# DAC.net
KiCad netlist of a schematic drawn in Altium Designer
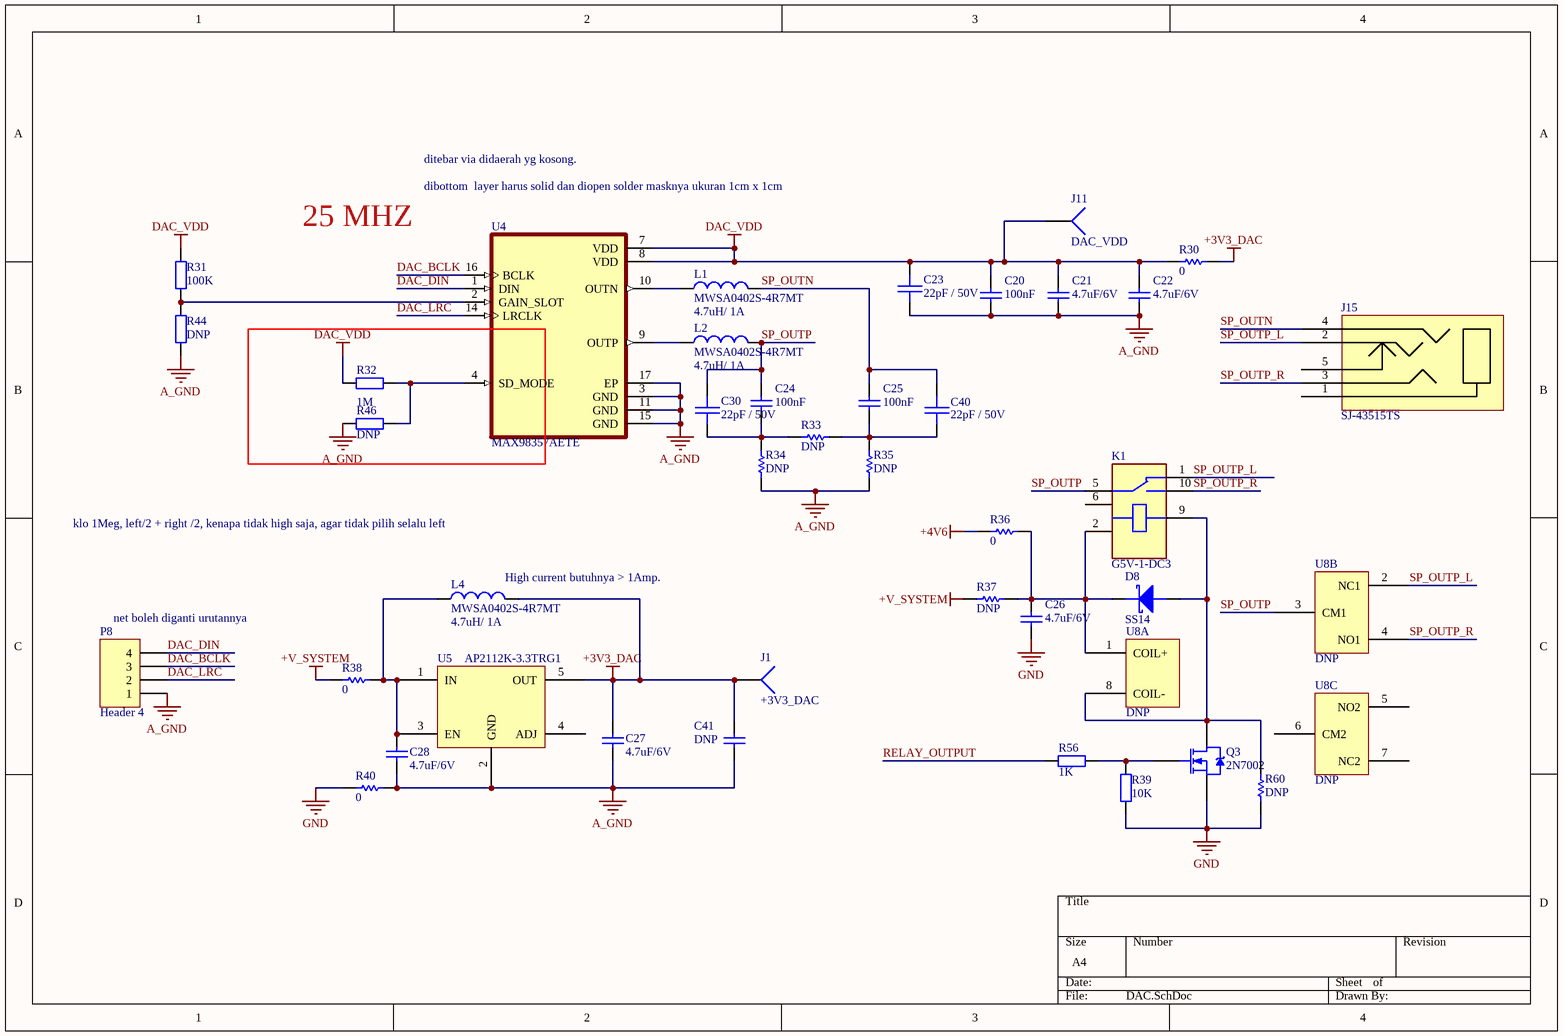
[diagram p0: DAC.SchDoc]

(export (version "E")
  (design (tool "Eeschema 10.0.6"))
  (components
    (comp (ref "C20")
      (value "100nF")
      (footprint "CR2012-0805")
      (description "Capacitor")
      (fields (field (name "PUBLISHER") "Altium Limited"))
      (libsource (lib "Miscellaneous Devices") (part "Cap"))
    )
    (comp (ref "C21")
      (value "4.7uF/6V")
      (footprint "CR2012-0805")
      (description "Capacitor")
      (fields (field (name "PUBLISHER") "Altium Limited"))
      (libsource (lib "Miscellaneous Devices") (part "Cap"))
    )
    (comp (ref "C22")
      (value "4.7uF/6V")
      (footprint "CR2012-0805")
      (description "Capacitor")
      (fields (field (name "PUBLISHER") "Altium Limited"))
      (libsource (lib "Miscellaneous Devices") (part "Cap"))
    )
    (comp (ref "C23")
      (value "22pF / 50V")
      (footprint "CR2012-0805")
      (description "Surface mount capacitor 0402")
      (libsource (lib "Vowstar_Basic_Device") (part "SMT_C_0402"))
    )
    (comp (ref "C24")
      (value "100nF")
      (footprint "CR2012-0805")
      (description "Capacitor")
      (fields (field (name "PUBLISHER") "Altium Limited"))
      (libsource (lib "Miscellaneous Devices") (part "Cap"))
    )
    (comp (ref "C25")
      (value "100nF")
      (footprint "CR2012-0805")
      (description "Capacitor")
      (fields (field (name "PUBLISHER") "Altium Limited"))
      (libsource (lib "Miscellaneous Devices") (part "Cap"))
    )
    (comp (ref "C26")
      (value "4.7uF/6V")
      (footprint "CR2012-0805")
      (description "Capacitor")
      (fields (field (name "PUBLISHER") "Altium Limited"))
      (libsource (lib "Miscellaneous Devices") (part "Cap"))
    )
    (comp (ref "C27")
      (value "4.7uF/6V")
      (footprint "CR2012-0805")
      (description "Capacitor (Semiconductor SIM Model)")
      (fields (field (name "PUBLISHER") "Altium Limited"))
      (libsource (lib "passive") (part "Cap Semi"))
    )
    (comp (ref "C28")
      (value "4.7uF/6V")
      (footprint "CR2012-0805")
      (description "Capacitor (Semiconductor SIM Model)")
      (fields (field (name "PUBLISHER") "Altium Limited"))
      (libsource (lib "passive") (part "Cap Semi"))
    )
    (comp (ref "C30")
      (value "22pF / 50V")
      (footprint "CR2012-0805")
      (description "Surface mount capacitor 0402")
      (libsource (lib "Vowstar_Basic_Device") (part "SMT_C_0402"))
    )
    (comp (ref "C40")
      (value "22pF / 50V")
      (footprint "CR2012-0805")
      (description "Surface mount capacitor 0402")
      (libsource (lib "Vowstar_Basic_Device") (part "SMT_C_0402"))
    )
    (comp (ref "C41")
      (value "DNP")
      (footprint "CR2012-0805")
      (description "Capacitor")
      (fields (field (name "PUBLISHER") "Altium Limited"))
      (libsource (lib "Miscellaneous Devices") (part "Cap"))
    )
    (comp (ref "D8")
      (value "SS14")
      (footprint "DO-214AC (SMA)")
      (description "Schottky Barrier Diodes")
      (fields (field (name "MANUFACTURER PART NUMBER") "SS18"))
      (libsource (lib "H2SCHALTIUM") (part "DIODE SCHOTTKY"))
    )
    (comp (ref "J1")
      (value "+3V3_DAC")
      (footprint "PIN1")
      (description "Socket")
      (fields (field (name "PUBLISHER") "Altium Limited"))
      (libsource (lib "Miscellaneous Connectors") (part "Socket"))
    )
    (comp (ref "J11")
      (value "DAC_VDD")
      (footprint "PIN1")
      (description "Socket")
      (fields (field (name "PUBLISHER") "Altium Limited"))
      (libsource (lib "Miscellaneous Connectors") (part "Socket"))
    )
    (comp (ref "J15")
      (value "SJ-43515TS")
      (footprint "SJ-435116")
      (description "SJ-43515TS 3.5 MM AUDIO JACK")
      (libsource (lib "passive") (part "SJ-43515TS"))
    )
    (comp (ref "K1")
      (value "G5V-1-DC3")
      (footprint "RELAY_G5V-1-DC5")
      (description "General Purpose Relay SPDT _1 Form C_ Through Hole")
      (fields (field (name "MF") "Omron Electronics") (field (name "MP") "G5V-1-DC5"))
      (libsource (lib "G5V-1-DC5") (part "G5V-1-DC5"))
    )
    (comp (ref "L1")
      (value "MWSA0402S-4R7MT")
      (footprint "IND4X4MM")
      (description "Inductor")
      (fields (field (name "ALTIUM_VALUE") "4.7uH/ 1A") (field (name "PUBLISHER") "Altium Limited"))
      (libsource (lib "passive") (part "Inductor"))
    )
    (comp (ref "L2")
      (value "MWSA0402S-4R7MT")
      (footprint "IND4X4MM")
      (description "Inductor")
      (fields (field (name "ALTIUM_VALUE") "4.7uH/ 1A") (field (name "PUBLISHER") "Altium Limited"))
      (libsource (lib "passive") (part "Inductor"))
    )
    (comp (ref "L4")
      (value "MWSA0402S-4R7MT")
      (footprint "IND4X4MM")
      (description "Inductor")
      (fields (field (name "ALTIUM_VALUE") "4.7uH/ 1A") (field (name "PUBLISHER") "Altium Limited"))
      (libsource (lib "passive") (part "Inductor"))
    )
    (comp (ref "P8")
      (value "Header 4")
      (footprint "HDR1X4")
      (description "Header, 4-Pin")
      (fields (field (name "PUBLISHER") "Altium Limited"))
      (libsource (lib "Miscellaneous Connectors") (part "Header 4"))
    )
    (comp (ref "Q3")
      (value "2N7002")
      (footprint "SOT-23/F2")
      (description "N CHANNEL MOSFET GENERIC SCH LIB")
      (fields (field (name "PART NUMBER") "2N7002ET1G") (field (name "MANUFACTURER") "ON Semiconductor"))
      (libsource (lib "passive") (part "NMOS_GENERIC_SOT23"))
    )
    (comp (ref "R30")
      (value "0")
      (footprint "JP1_SMD")
      (description "Semiconductor Resistor")
      (fields (field (name "PUBLISHER") "Altium Limited"))
      (libsource (lib "passive") (part "Res Semi"))
    )
    (comp (ref "R31")
      (value "100K")
      (footprint "JP2_SMD")
      (description "Resistor")
      (fields (field (name "PUBLISHER") "Altium Limited"))
      (libsource (lib "Miscellaneous Devices") (part "Res2"))
    )
    (comp (ref "R32")
      (value "1M")
      (footprint "JP2_SMD")
      (description "Resistor")
      (fields (field (name "PUBLISHER") "Altium Limited"))
      (libsource (lib "") (part "Res2_2"))
    )
    (comp (ref "R33")
      (value "DNP")
      (footprint "JP2_SMD")
      (description "Semiconductor Resistor")
      (fields (field (name "PUBLISHER") "Altium Limited"))
      (libsource (lib "passive") (part "Res Semi"))
    )
    (comp (ref "R34")
      (value "DNP")
      (footprint "JP2_SMD")
      (description "Semiconductor Resistor")
      (fields (field (name "PUBLISHER") "Altium Limited"))
      (libsource (lib "passive") (part "Res Semi"))
    )
    (comp (ref "R35")
      (value "DNP")
      (footprint "JP2_SMD")
      (description "Semiconductor Resistor")
      (fields (field (name "PUBLISHER") "Altium Limited"))
      (libsource (lib "passive") (part "Res Semi"))
    )
    (comp (ref "R36")
      (value "0")
      (footprint "JP1_SMD")
      (description "Semiconductor Resistor")
      (fields (field (name "PUBLISHER") "Altium Limited"))
      (libsource (lib "passive") (part "Res Semi"))
    )
    (comp (ref "R37")
      (value "DNP")
      (footprint "JP1_SMD")
      (description "Semiconductor Resistor")
      (fields (field (name "PUBLISHER") "Altium Limited"))
      (libsource (lib "passive") (part "Res Semi"))
    )
    (comp (ref "R38")
      (value "0")
      (footprint "JP1_SMD")
      (description "Semiconductor Resistor")
      (fields (field (name "PUBLISHER") "Altium Limited"))
      (libsource (lib "passive") (part "Res Semi"))
    )
    (comp (ref "R39")
      (value "10K")
      (footprint "CR2012-0805")
      (description "Resistor")
      (fields (field (name "PUBLISHER") "Altium Limited"))
      (libsource (lib "Miscellaneous Devices") (part "Res2"))
    )
    (comp (ref "R40")
      (value "0")
      (footprint "JP1_SMD")
      (description "Semiconductor Resistor")
      (fields (field (name "PUBLISHER") "Altium Limited"))
      (libsource (lib "passive") (part "Res Semi"))
    )
    (comp (ref "R44")
      (value "DNP")
      (footprint "JP2_SMD")
      (description "Resistor")
      (fields (field (name "PUBLISHER") "Altium Limited"))
      (libsource (lib "Miscellaneous Devices") (part "Res2"))
    )
    (comp (ref "R46")
      (value "DNP")
      (footprint "JP2_SMD")
      (description "Resistor")
      (fields (field (name "PUBLISHER") "Altium Limited"))
      (libsource (lib "") (part "Res2_1"))
    )
    (comp (ref "R56")
      (value "1K")
      (footprint "CR2012-0805")
      (description "Resistor")
      (fields (field (name "PUBLISHER") "Altium Limited"))
      (libsource (lib "") (part "Res2_1"))
    )
    (comp (ref "R60")
      (value "DNP")
      (footprint "JP1_SMD")
      (description "Semiconductor Resistor")
      (fields (field (name "PUBLISHER") "Altium Limited"))
      (libsource (lib "passive") (part "Res Semi"))
    )
    (comp (ref "U4")
      (value "MAX98357AETE")
      (footprint "QFN50P300X300X80-17N")
      (description "Audio Amp Speaker 1-CH Mono 3.2W Class-D 16-Pin TQFN EP T/R")
      (fields (field (name "MF") "Maxim Integrated"))
      (libsource (lib "MAX98357AETE") (part "MAX98357AETE"))
    )
    (comp (ref "U5")
      (value "AP2112K-3.3TRG1")
      (footprint "SOT-23-5")
      (description "IC REG LDO ADJ .15A SOT25-5")
      (fields
        (field (name "MANUFACTURER") "Diodes Inc")
        (field (name "MANUFACTURER PART NUMBER") "AP2112K-3.3TRG1")
      )
      (libsource (lib "active") (part "AP7311"))
    )
    (comp (ref "U8")
      (value "DNP")
      (footprint "EC2-5NU")
      (description "EC2-5NU Miniature Signal Relays 4 Volt Control")
      (libsource (lib "passive") (part "EC2-5NU"))
    )
  )
  (nets
    (net (code "1") (name "+3V3_DAC") (class "Default")
      (node (ref "C27") (pin "2") (pinfunction "2_2") (pintype "passive"))
      (node (ref "C41") (pin "2") (pinfunction "2_2") (pintype "passive"))
      (node (ref "J1") (pin "1") (pinfunction "1_1") (pintype "passive"))
      (node (ref "L4") (pin "2") (pinfunction "2_2") (pintype "passive"))
      (node (ref "R30") (pin "2") (pinfunction "2_2") (pintype "passive"))
      (node (ref "U5") (pin "5") (pinfunction "OUT_5") (pintype "passive"))
    )
    (net (code "2") (name "+4V6") (class "Default")
      (node (ref "R36") (pin "1") (pinfunction "1_1") (pintype "passive"))
    )
    (net (code "3") (name "+V_SYSTEM") (class "Default")
      (node (ref "R37") (pin "1") (pinfunction "1_1") (pintype "passive"))
      (node (ref "R38") (pin "1") (pinfunction "1_1") (pintype "passive"))
    )
    (net (code "4") (name "/DAC_BCLK") (class "Default")
      (node (ref "P8") (pin "3") (pinfunction "3_3") (pintype "passive"))
      (node (ref "U4") (pin "16") (pinfunction "BCLK_16") (pintype "input"))
    )
    (net (code "5") (name "/DAC_DIN") (class "Default")
      (node (ref "P8") (pin "4") (pinfunction "4_4") (pintype "passive"))
      (node (ref "U4") (pin "1") (pinfunction "DIN_1") (pintype "input"))
    )
    (net (code "6") (name "/DAC_LRC") (class "Default")
      (node (ref "P8") (pin "2") (pinfunction "2_2") (pintype "passive"))
      (node (ref "U4") (pin "14") (pinfunction "LRCLK_14") (pintype "input"))
    )
    (net (code "7") (name "/RELAY_OUTPUT") (class "Default")
      (node (ref "R56") (pin "2") (pinfunction "2_2") (pintype "passive"))
    )
    (net (code "8") (name "/SP_OUTN") (class "Default")
      (node (ref "C25") (pin "2") (pinfunction "2_2") (pintype "passive"))
      (node (ref "C40") (pin "1") (pinfunction "1_1") (pintype "passive"))
      (node (ref "J15") (pin "4") (pinfunction "4_4") (pintype "passive"))
      (node (ref "L1") (pin "2") (pinfunction "2_2") (pintype "passive"))
    )
    (net (code "9") (name "/SP_OUTP") (class "Default")
      (node (ref "C24") (pin "2") (pinfunction "2_2") (pintype "passive"))
      (node (ref "C30") (pin "1") (pinfunction "1_1") (pintype "passive"))
      (node (ref "K1") (pin "5") (pinfunction "COM_5") (pintype "passive"))
      (node (ref "L2") (pin "2") (pinfunction "2_2") (pintype "passive"))
      (node (ref "U8") (pin "3") (pinfunction "CM1_3") (pintype "passive"))
    )
    (net (code "10") (name "/SP_OUTP_L") (class "Default")
      (node (ref "J15") (pin "2") (pinfunction "2_2") (pintype "passive"))
      (node (ref "K1") (pin "1") (pinfunction "NC_1") (pintype "passive"))
      (node (ref "U8") (pin "2") (pinfunction "NC1_2") (pintype "passive"))
    )
    (net (code "11") (name "/SP_OUTP_R") (class "Default")
      (node (ref "J15") (pin "3") (pinfunction "3_3") (pintype "passive"))
      (node (ref "K1") (pin "10") (pinfunction "NO_10") (pintype "passive"))
      (node (ref "U8") (pin "4") (pinfunction "NO1_4") (pintype "passive"))
    )
    (net (code "12") (name "A_GND") (class "Default")
      (node (ref "C20") (pin "1") (pinfunction "1_1") (pintype "passive"))
      (node (ref "C21") (pin "1") (pinfunction "1_1") (pintype "passive"))
      (node (ref "C22") (pin "1") (pinfunction "1_1") (pintype "passive"))
      (node (ref "C23") (pin "2") (pinfunction "2_2") (pintype "passive"))
      (node (ref "C27") (pin "1") (pinfunction "1_1") (pintype "passive"))
      (node (ref "C28") (pin "1") (pinfunction "1_1") (pintype "passive"))
      (node (ref "C41") (pin "1") (pinfunction "1_1") (pintype "passive"))
      (node (ref "P8") (pin "1") (pinfunction "1_1") (pintype "passive"))
      (node (ref "R34") (pin "1") (pinfunction "1_1") (pintype "passive"))
      (node (ref "R35") (pin "1") (pinfunction "1_1") (pintype "passive"))
      (node (ref "R40") (pin "2") (pinfunction "2_2") (pintype "passive"))
      (node (ref "R44") (pin "1") (pinfunction "1_1") (pintype "passive"))
      (node (ref "R46") (pin "2") (pinfunction "2_2") (pintype "passive"))
      (node (ref "U4") (pin "11") (pinfunction "GND_11") (pintype "power_in"))
      (node (ref "U4") (pin "15") (pinfunction "GND_15") (pintype "power_in"))
      (node (ref "U4") (pin "17") (pinfunction "EP_17") (pintype "power_in"))
      (node (ref "U4") (pin "3") (pinfunction "GND_3") (pintype "power_in"))
      (node (ref "U5") (pin "2") (pinfunction "GND_2") (pintype "passive"))
    )
    (net (code "13") (name "DAC_VDD") (class "Default")
      (node (ref "C20") (pin "2") (pinfunction "2_2") (pintype "passive"))
      (node (ref "C21") (pin "2") (pinfunction "2_2") (pintype "passive"))
      (node (ref "C22") (pin "2") (pinfunction "2_2") (pintype "passive"))
      (node (ref "C23") (pin "1") (pinfunction "1_1") (pintype "passive"))
      (node (ref "J11") (pin "1") (pinfunction "1_1") (pintype "passive"))
      (node (ref "R30") (pin "1") (pinfunction "1_1") (pintype "passive"))
      (node (ref "R31") (pin "2") (pinfunction "2_2") (pintype "passive"))
      (node (ref "R32") (pin "1") (pinfunction "1_1") (pintype "passive"))
      (node (ref "U4") (pin "7") (pinfunction "VDD_7") (pintype "power_in"))
      (node (ref "U4") (pin "8") (pinfunction "VDD_8") (pintype "power_in"))
    )
    (net (code "14") (name "GND") (class "Default")
      (node (ref "C26") (pin "1") (pinfunction "1_1") (pintype "passive"))
      (node (ref "Q3") (pin "S") (pinfunction "S_S") (pintype "passive"))
      (node (ref "R39") (pin "1") (pinfunction "1_1") (pintype "passive"))
      (node (ref "R40") (pin "1") (pinfunction "1_1") (pintype "passive"))
      (node (ref "R60") (pin "1") (pinfunction "1_1") (pintype "passive"))
    )
    (net (code "15") (name "Net-(C24-Pad1)") (class "Default")
      (node (ref "C24") (pin "1") (pinfunction "1_1") (pintype "passive"))
      (node (ref "C30") (pin "2") (pinfunction "2_2") (pintype "passive"))
      (node (ref "R33") (pin "1") (pinfunction "1_1") (pintype "passive"))
      (node (ref "R34") (pin "2") (pinfunction "2_2") (pintype "passive"))
    )
    (net (code "16") (name "Net-(C25-Pad1)") (class "Default")
      (node (ref "C25") (pin "1") (pinfunction "1_1") (pintype "passive"))
      (node (ref "C40") (pin "2") (pinfunction "2_2") (pintype "passive"))
      (node (ref "R33") (pin "2") (pinfunction "2_2") (pintype "passive"))
      (node (ref "R35") (pin "2") (pinfunction "2_2") (pintype "passive"))
    )
    (net (code "17") (name "Net-(D8-A)") (class "Default")
      (node (ref "D8") (pin "1") (pinfunction "A_1") (pintype "passive"))
      (node (ref "K1") (pin "9") (pinfunction "C2_9") (pintype "passive"))
      (node (ref "Q3") (pin "D") (pinfunction "D_D") (pintype "passive"))
      (node (ref "R60") (pin "2") (pinfunction "2_2") (pintype "passive"))
      (node (ref "U8") (pin "8") (pinfunction "COIL-_8") (pintype "passive"))
    )
    (net (code "18") (name "Net-(D8-K)") (class "Default")
      (node (ref "C26") (pin "2") (pinfunction "2_2") (pintype "passive"))
      (node (ref "D8") (pin "2") (pinfunction "K_2") (pintype "passive"))
      (node (ref "K1") (pin "2") (pinfunction "C1_2") (pintype "passive"))
      (node (ref "R36") (pin "2") (pinfunction "2_2") (pintype "passive"))
      (node (ref "R37") (pin "2") (pinfunction "2_2") (pintype "passive"))
      (node (ref "U8") (pin "1") (pinfunction "COIL+_1") (pintype "passive"))
    )
    (net (code "19") (name "Net-(Q3-PadG)") (class "Default")
      (node (ref "Q3") (pin "G") (pinfunction "G_G") (pintype "passive"))
      (node (ref "R39") (pin "2") (pinfunction "2_2") (pintype "passive"))
      (node (ref "R56") (pin "1") (pinfunction "1_1") (pintype "passive"))
    )
    (net (code "20") (name "Net-(U4-GAIN_SLOT)") (class "Default")
      (node (ref "R31") (pin "1") (pinfunction "1_1") (pintype "passive"))
      (node (ref "R44") (pin "2") (pinfunction "2_2") (pintype "passive"))
      (node (ref "U4") (pin "2") (pinfunction "GAIN_SLOT_2") (pintype "input"))
    )
    (net (code "21") (name "Net-(U4-OUTN)") (class "Default")
      (node (ref "L1") (pin "1") (pinfunction "1_1") (pintype "passive"))
      (node (ref "U4") (pin "10") (pinfunction "OUTN_10") (pintype "output"))
    )
    (net (code "22") (name "Net-(U4-OUTP)") (class "Default")
      (node (ref "L2") (pin "1") (pinfunction "1_1") (pintype "passive"))
      (node (ref "U4") (pin "9") (pinfunction "OUTP_9") (pintype "output"))
    )
    (net (code "23") (name "Net-(U4-SD_MODE)") (class "Default")
      (node (ref "R32") (pin "2") (pinfunction "2_2") (pintype "passive"))
      (node (ref "R46") (pin "1") (pinfunction "1_1") (pintype "passive"))
      (node (ref "U4") (pin "4") (pinfunction "SD_MODE_4") (pintype "input"))
    )
    (net (code "24") (name "Net-(U5-EN)") (class "Default")
      (node (ref "C28") (pin "2") (pinfunction "2_2") (pintype "passive"))
      (node (ref "L4") (pin "1") (pinfunction "1_1") (pintype "passive"))
      (node (ref "R38") (pin "2") (pinfunction "2_2") (pintype "passive"))
      (node (ref "U5") (pin "1") (pinfunction "IN_1") (pintype "passive"))
      (node (ref "U5") (pin "3") (pinfunction "EN_3") (pintype "passive"))
    )
    (net (code "25") (name "unconnected-(J15-Pad1)") (class "Default")
      (node (ref "J15") (pin "1") (pinfunction "1_1") (pintype "passive"))
    )
    (net (code "26") (name "unconnected-(J15-Pad5)") (class "Default")
      (node (ref "J15") (pin "5") (pinfunction "5_5") (pintype "passive"))
    )
    (net (code "27") (name "unconnected-(K1-COM-Pad6)") (class "Default")
      (node (ref "K1") (pin "6") (pinfunction "COM_6") (pintype "passive"))
    )
    (net (code "28") (name "unconnected-(U5-ADJ-Pad4)") (class "Default")
      (node (ref "U5") (pin "4") (pinfunction "ADJ_4") (pintype "passive"))
    )
    (net (code "29") (name "unconnected-(U8C-CM2-Pad6)") (class "Default")
      (node (ref "U8") (pin "6") (pinfunction "CM2_6") (pintype "passive"))
    )
    (net (code "30") (name "unconnected-(U8C-NC2-Pad7)") (class "Default")
      (node (ref "U8") (pin "7") (pinfunction "NC2_7") (pintype "passive"))
    )
    (net (code "31") (name "unconnected-(U8C-NO2-Pad5)") (class "Default")
      (node (ref "U8") (pin "5") (pinfunction "NO2_5") (pintype "passive"))
    )
  )
)
